# FOC_MCU.net
KiCad netlist of a schematic drawn in Altium Designer
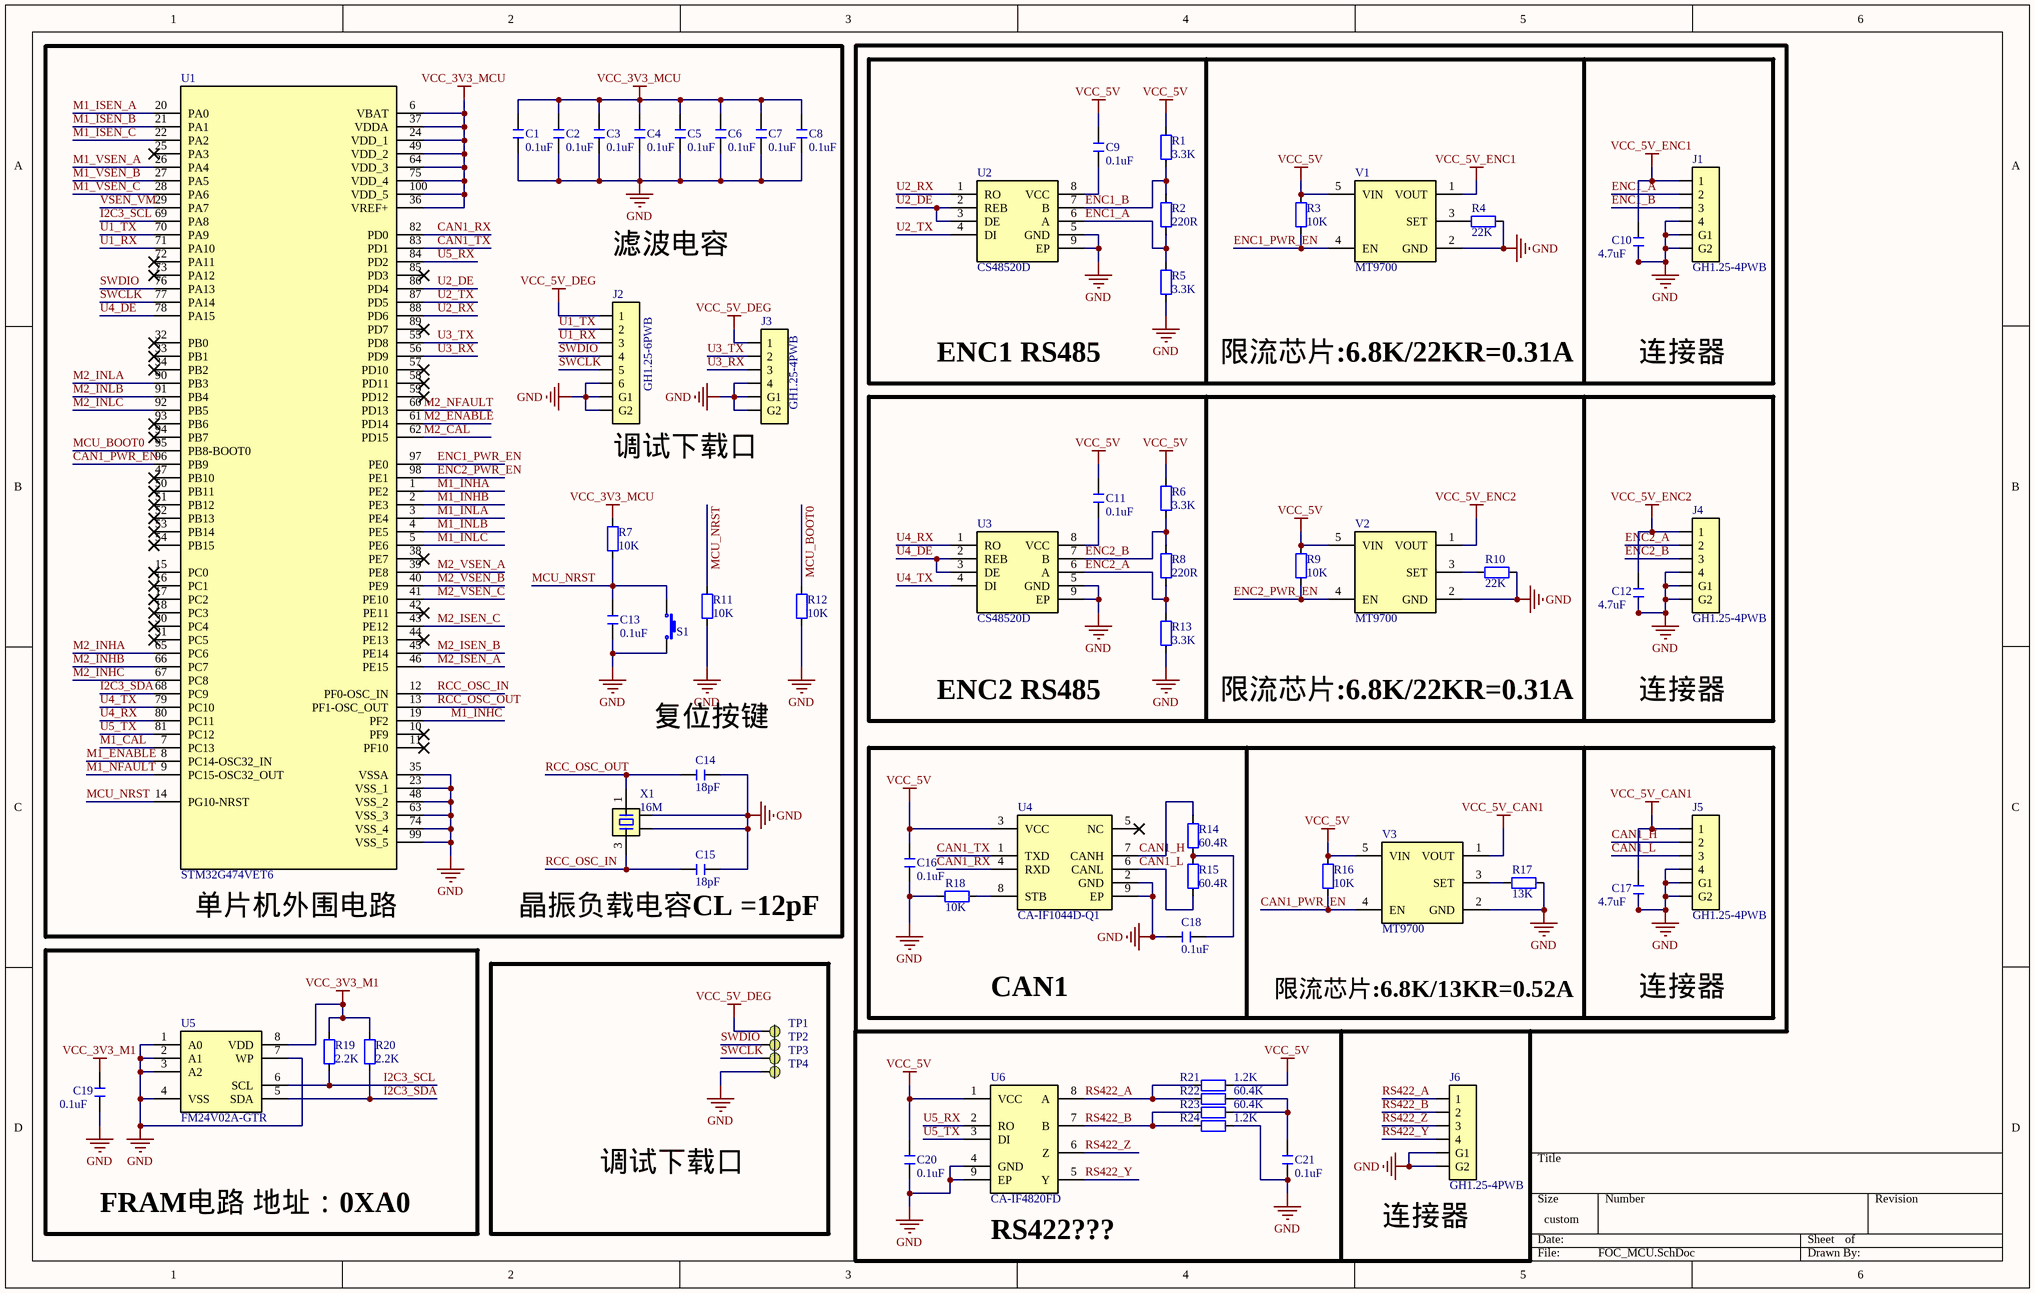
[diagram p0: FOC_MCU.SchDoc]

(export (version "E")
  (design (tool "Eeschema 10.0.6"))
  (components
    (comp (ref "C1")
      (value "0.1uF")
      (footprint "C 0603_L")
      (description "贴片电容")
      (libsource (lib "0.1 电阻_电容_电感") (part "C"))
    )
    (comp (ref "C2")
      (value "0.1uF")
      (footprint "C 0603_L")
      (description "贴片电容")
      (libsource (lib "0.1 电阻_电容_电感") (part "C"))
    )
    (comp (ref "C3")
      (value "0.1uF")
      (footprint "C 0603_L")
      (description "贴片电容")
      (libsource (lib "0.1 电阻_电容_电感") (part "C"))
    )
    (comp (ref "C4")
      (value "0.1uF")
      (footprint "C 0603_L")
      (description "贴片电容")
      (libsource (lib "0.1 电阻_电容_电感") (part "C"))
    )
    (comp (ref "C5")
      (value "0.1uF")
      (footprint "C 0603_L")
      (description "贴片电容")
      (libsource (lib "0.1 电阻_电容_电感") (part "C"))
    )
    (comp (ref "C6")
      (value "0.1uF")
      (footprint "C 0603_L")
      (description "贴片电容")
      (libsource (lib "0.1 电阻_电容_电感") (part "C"))
    )
    (comp (ref "C7")
      (value "0.1uF")
      (footprint "C 0603_L")
      (description "贴片电容")
      (libsource (lib "0.1 电阻_电容_电感") (part "C"))
    )
    (comp (ref "C8")
      (value "0.1uF")
      (footprint "C 0603_L")
      (description "贴片电容")
      (libsource (lib "0.1 电阻_电容_电感") (part "C"))
    )
    (comp (ref "C9")
      (value "0.1uF")
      (footprint "C 0603_L")
      (description "贴片电容")
      (libsource (lib "0.1 电阻_电容_电感") (part "C"))
    )
    (comp (ref "C10")
      (value "4.7uF")
      (footprint "C 0603_L")
      (description "贴片电容")
      (libsource (lib "0.1 电阻_电容_电感") (part "C"))
    )
    (comp (ref "C11")
      (value "0.1uF")
      (footprint "C 0603_L")
      (description "贴片电容")
      (libsource (lib "0.1 电阻_电容_电感") (part "C"))
    )
    (comp (ref "C12")
      (value "4.7uF")
      (footprint "C 0603_L")
      (description "贴片电容")
      (libsource (lib "0.1 电阻_电容_电感") (part "C"))
    )
    (comp (ref "C13")
      (value "0.1uF")
      (footprint "C 0603_L")
      (description "贴片电容")
      (libsource (lib "0.1 电阻_电容_电感") (part "C"))
    )
    (comp (ref "C14")
      (value "18pF")
      (footprint "C 0603_L")
      (description "贴片电容")
      (libsource (lib "0.1 电阻_电容_电感") (part "C"))
    )
    (comp (ref "C15")
      (value "18pF")
      (footprint "C 0603_L")
      (description "贴片电容")
      (libsource (lib "0.1 电阻_电容_电感") (part "C"))
    )
    (comp (ref "C16")
      (value "0.1uF")
      (footprint "C 0603_L")
      (description "贴片电容")
      (libsource (lib "0.1 电阻_电容_电感") (part "C"))
    )
    (comp (ref "C17")
      (value "4.7uF")
      (footprint "C 0603_L")
      (description "贴片电容")
      (libsource (lib "0.1 电阻_电容_电感") (part "C"))
    )
    (comp (ref "C18")
      (value "0.1uF")
      (footprint "C 0603_L")
      (description "贴片电容")
      (libsource (lib "0.1 电阻_电容_电感") (part "C"))
    )
    (comp (ref "C19")
      (value "0.1uF")
      (footprint "C 0603_L")
      (description "贴片电容")
      (libsource (lib "0.1 电阻_电容_电感") (part "C"))
    )
    (comp (ref "C20")
      (value "0.1uF")
      (footprint "C 0603_L")
      (description "贴片电容")
      (libsource (lib "0.1 电阻_电容_电感") (part "C"))
    )
    (comp (ref "C21")
      (value "0.1uF")
      (footprint "C 0603_L")
      (description "贴片电容")
      (libsource (lib "0.1 电阻_电容_电感") (part "C"))
    )
    (comp (ref "J1")
      (value "GH1.25-4PWB")
      (footprint "GH1.25-4PWB")
      (description "GH1.25-4P 卧贴")
      (libsource (lib "3.5 连接器") (part "GH1.25-4PWB"))
    )
    (comp (ref "J2")
      (value "GH1.25-6PWB")
      (footprint "GH1.25-6PWB")
      (description "GH1.25-6P 卧贴")
      (libsource (lib "3.5 连接器") (part "GH1.25-6PWB"))
    )
    (comp (ref "J3")
      (value "GH1.25-4PWB")
      (footprint "GH1.25-4PWB")
      (description "GH1.25-4P 卧贴")
      (libsource (lib "3.5 连接器") (part "GH1.25-4PWB"))
    )
    (comp (ref "J4")
      (value "GH1.25-4PWB")
      (footprint "GH1.25-4PWB")
      (description "GH1.25-4P 卧贴")
      (libsource (lib "3.5 连接器") (part "GH1.25-4PWB"))
    )
    (comp (ref "J5")
      (value "GH1.25-4PWB")
      (footprint "GH1.25-4PWB")
      (description "GH1.25-4P 卧贴")
      (libsource (lib "3.5 连接器") (part "GH1.25-4PWB"))
    )
    (comp (ref "J6")
      (value "GH1.25-4PWB")
      (footprint "GH1.25-4PWB")
      (description "GH1.25-4P 卧贴")
      (libsource (lib "3.5 连接器") (part "GH1.25-4PWB"))
    )
    (comp (ref "R1")
      (value "3.3K")
      (footprint "R 0603_L")
      (description "贴片电阻")
      (libsource (lib "") (part "R_1"))
    )
    (comp (ref "R2")
      (value "220R")
      (footprint "R 0603_L")
      (description "贴片电阻")
      (libsource (lib "") (part "R_1"))
    )
    (comp (ref "R3")
      (value "10K")
      (footprint "R 0603_L")
      (description "贴片电阻")
      (libsource (lib "") (part "R_1"))
    )
    (comp (ref "R4")
      (value "22K")
      (footprint "R 0603_L")
      (description "贴片电阻")
      (libsource (lib "0.1 电阻_电容_电感") (part "R"))
    )
    (comp (ref "R5")
      (value "3.3K")
      (footprint "R 0603_L")
      (description "贴片电阻")
      (libsource (lib "") (part "R_1"))
    )
    (comp (ref "R6")
      (value "3.3K")
      (footprint "R 0603_L")
      (description "贴片电阻")
      (libsource (lib "") (part "R_1"))
    )
    (comp (ref "R7")
      (value "10K")
      (footprint "R 0603_L")
      (description "贴片电阻")
      (libsource (lib "") (part "R_2"))
    )
    (comp (ref "R8")
      (value "220R")
      (footprint "R 0603_L")
      (description "贴片电阻")
      (libsource (lib "") (part "R_1"))
    )
    (comp (ref "R9")
      (value "10K")
      (footprint "R 0603_L")
      (description "贴片电阻")
      (libsource (lib "") (part "R_1"))
    )
    (comp (ref "R10")
      (value "22K")
      (footprint "R 0603_L")
      (description "贴片电阻")
      (libsource (lib "0.1 电阻_电容_电感") (part "R"))
    )
    (comp (ref "R11")
      (value "10K")
      (footprint "R 0603_L")
      (description "贴片电阻")
      (libsource (lib "") (part "R_2"))
    )
    (comp (ref "R12")
      (value "10K")
      (footprint "R 0603_L")
      (description "贴片电阻")
      (libsource (lib "") (part "R_2"))
    )
    (comp (ref "R13")
      (value "3.3K")
      (footprint "R 0603_L")
      (description "贴片电阻")
      (libsource (lib "") (part "R_1"))
    )
    (comp (ref "R14")
      (value "60.4R")
      (footprint "R 0603_L")
      (description "贴片电阻")
      (libsource (lib "") (part "R_2"))
    )
    (comp (ref "R15")
      (value "60.4R")
      (footprint "R 0603_L")
      (description "贴片电阻")
      (libsource (lib "") (part "R_2"))
    )
    (comp (ref "R16")
      (value "10K")
      (footprint "R 0603_L")
      (description "贴片电阻")
      (libsource (lib "") (part "R_1"))
    )
    (comp (ref "R17")
      (value "13K")
      (footprint "R 0603_L")
      (description "贴片电阻")
      (libsource (lib "0.1 电阻_电容_电感") (part "R"))
    )
    (comp (ref "R18")
      (value "10K")
      (footprint "R 0603_L")
      (description "贴片电阻")
      (libsource (lib "0.1 电阻_电容_电感") (part "R"))
    )
    (comp (ref "R19")
      (value "2.2K")
      (footprint "R 0603_L")
      (description "贴片电阻")
      (libsource (lib "") (part "R_1"))
    )
    (comp (ref "R20")
      (value "2.2K")
      (footprint "R 0603_L")
      (description "贴片电阻")
      (libsource (lib "") (part "R_1"))
    )
    (comp (ref "R21")
      (value "1.2K")
      (footprint "R 0603_L")
      (description "贴片电阻")
      (libsource (lib "0.1 电阻_电容_电感") (part "R"))
    )
    (comp (ref "R22")
      (value "60.4K")
      (footprint "R 0603_L")
      (description "贴片电阻")
      (libsource (lib "0.1 电阻_电容_电感") (part "R"))
    )
    (comp (ref "R23")
      (value "60.4K")
      (footprint "R 0603_L")
      (description "贴片电阻")
      (libsource (lib "0.1 电阻_电容_电感") (part "R"))
    )
    (comp (ref "R24")
      (value "1.2K")
      (footprint "R 0603_L")
      (description "贴片电阻")
      (libsource (lib "0.1 电阻_电容_电感") (part "R"))
    )
    (comp (ref "S1")
      (value "TS-1089S-02526")
      (footprint "SMD_TS-1089S")
      (libsource (lib "0.7 按键开关") (part "TS-1089S-02526"))
    )
    (comp (ref "TP1") (value "~") (footprint "TP_RECT_2x2") (libsource (lib "0.5 测试点-焊盘") (part "TP")))
    (comp (ref "TP2") (value "~") (footprint "TP_RECT_2x2") (libsource (lib "0.5 测试点-焊盘") (part "TP")))
    (comp (ref "TP3") (value "~") (footprint "TP_RECT_2x2") (libsource (lib "0.5 测试点-焊盘") (part "TP")))
    (comp (ref "TP4") (value "~") (footprint "TP_RECT_2x2") (libsource (lib "0.5 测试点-焊盘") (part "TP")))
    (comp (ref "U1")
      (value "STM32G474VET6")
      (footprint "LQFP100_L")
      (description "STM32G4系列微处理器")
      (libsource (lib "1.0 微处理器") (part "STM32G474VET6"))
    )
    (comp (ref "U2")
      (value "CS48520D")
      (footprint "DFN65P300X75-9N")
      (description "RS485")
      (libsource (lib "1.4 通信芯片") (part "CS48520D"))
    )
    (comp (ref "U3")
      (value "CS48520D")
      (footprint "DFN65P300X75-9N")
      (description "RS485")
      (libsource (lib "1.4 通信芯片") (part "CS48520D"))
    )
    (comp (ref "U4")
      (value "CA-IF1044D-Q1")
      (footprint "DFN65P300X75-9N")
      (description "CAN收发器，5Mbps")
      (libsource (lib "1.4 通信芯片") (part "CA-IF1044D-Q1"))
    )
    (comp (ref "U5")
      (value "FM24V02A-GTR")
      (footprint "SOIC-8N")
      (libsource (lib "1.5 存储芯片") (part "FM24V02A-GTR"))
    )
    (comp (ref "U6")
      (value "CA-IF4820FD")
      (footprint "DFN65P300X75-9N")
      (description "RS422，3.3V/5V，20Mbps")
      (libsource (lib "1.4 通信芯片") (part "CA-IF4820FD"))
    )
    (comp (ref "V1")
      (value "MT9700")
      (footprint "SOT-23-5")
      (description "功率电子开关")
      (libsource (lib "1.2 电源芯片") (part "MT9700"))
    )
    (comp (ref "V2")
      (value "MT9700")
      (footprint "SOT-23-5")
      (description "功率电子开关")
      (libsource (lib "1.2 电源芯片") (part "MT9700"))
    )
    (comp (ref "V3")
      (value "MT9700")
      (footprint "SOT-23-5")
      (description "功率电子开关")
      (libsource (lib "1.2 电源芯片") (part "MT9700"))
    )
    (comp (ref "X1")
      (value "16M")
      (footprint "OSC 2016-4P")
      (description "4脚无源晶振，负载电容12pF")
      (libsource (lib "0.9 晶振") (part "X201616MOB4SI"))
    )
  )
  (nets
    (net (code "1") (name "/CAN1_H") (class "Default")
      (node (ref "J5") (pin "2") (pinfunction "2_2") (pintype "passive"))
      (node (ref "R14") (pin "1") (pinfunction "1_1") (pintype "passive"))
      (node (ref "U4") (pin "7") (pinfunction "CANH_7") (pintype "passive"))
    )
    (net (code "2") (name "/CAN1_L") (class "Default")
      (node (ref "J5") (pin "3") (pinfunction "3_3") (pintype "passive"))
      (node (ref "R15") (pin "2") (pinfunction "2_2") (pintype "passive"))
      (node (ref "U4") (pin "6") (pinfunction "CANL_6") (pintype "passive"))
    )
    (net (code "3") (name "/CAN1_PWR_EN") (class "Default")
      (node (ref "R16") (pin "1") (pinfunction "1_1") (pintype "passive"))
      (node (ref "U1") (pin "96") (pinfunction "PB9_96") (pintype "passive"))
      (node (ref "V3") (pin "4") (pinfunction "EN_4") (pintype "passive"))
    )
    (net (code "4") (name "/CAN1_RX") (class "Default")
      (node (ref "U1") (pin "82") (pinfunction "PD0_82") (pintype "passive"))
      (node (ref "U4") (pin "4") (pinfunction "RXD_4") (pintype "power_in"))
    )
    (net (code "5") (name "/CAN1_TX") (class "Default")
      (node (ref "U1") (pin "83") (pinfunction "PD1_83") (pintype "passive"))
      (node (ref "U4") (pin "1") (pinfunction "TXD_1") (pintype "power_in"))
    )
    (net (code "6") (name "/ENC1_A") (class "Default")
      (node (ref "J1") (pin "2") (pinfunction "2_2") (pintype "passive"))
      (node (ref "R2") (pin "1") (pinfunction "1_1") (pintype "passive"))
      (node (ref "R5") (pin "2") (pinfunction "2_2") (pintype "passive"))
      (node (ref "U2") (pin "6") (pinfunction "A_6") (pintype "passive"))
    )
    (net (code "7") (name "/ENC1_B") (class "Default")
      (node (ref "J1") (pin "3") (pinfunction "3_3") (pintype "passive"))
      (node (ref "R1") (pin "1") (pinfunction "1_1") (pintype "passive"))
      (node (ref "R2") (pin "2") (pinfunction "2_2") (pintype "passive"))
      (node (ref "U2") (pin "7") (pinfunction "B_7") (pintype "passive"))
    )
    (net (code "8") (name "/ENC1_PWR_EN") (class "Default")
      (node (ref "R3") (pin "1") (pinfunction "1_1") (pintype "passive"))
      (node (ref "U1") (pin "97") (pinfunction "PE0_97") (pintype "passive"))
      (node (ref "V1") (pin "4") (pinfunction "EN_4") (pintype "passive"))
    )
    (net (code "9") (name "/ENC2_A") (class "Default")
      (node (ref "J4") (pin "2") (pinfunction "2_2") (pintype "passive"))
      (node (ref "R13") (pin "2") (pinfunction "2_2") (pintype "passive"))
      (node (ref "R8") (pin "1") (pinfunction "1_1") (pintype "passive"))
      (node (ref "U3") (pin "6") (pinfunction "A_6") (pintype "passive"))
    )
    (net (code "10") (name "/ENC2_B") (class "Default")
      (node (ref "J4") (pin "3") (pinfunction "3_3") (pintype "passive"))
      (node (ref "R6") (pin "1") (pinfunction "1_1") (pintype "passive"))
      (node (ref "R8") (pin "2") (pinfunction "2_2") (pintype "passive"))
      (node (ref "U3") (pin "7") (pinfunction "B_7") (pintype "passive"))
    )
    (net (code "11") (name "/ENC2_PWR_EN") (class "Default")
      (node (ref "R9") (pin "1") (pinfunction "1_1") (pintype "passive"))
      (node (ref "U1") (pin "98") (pinfunction "PE1_98") (pintype "passive"))
      (node (ref "V2") (pin "4") (pinfunction "EN_4") (pintype "passive"))
    )
    (net (code "12") (name "/I2C3_SCL") (class "Default")
      (node (ref "R19") (pin "1") (pinfunction "1_1") (pintype "passive"))
      (node (ref "U1") (pin "69") (pinfunction "PA8_69") (pintype "passive"))
      (node (ref "U5") (pin "6") (pinfunction "SCL_6") (pintype "passive"))
    )
    (net (code "13") (name "/I2C3_SDA") (class "Default")
      (node (ref "R20") (pin "1") (pinfunction "1_1") (pintype "passive"))
      (node (ref "U1") (pin "68") (pinfunction "PC9_68") (pintype "passive"))
      (node (ref "U5") (pin "5") (pinfunction "SDA_5") (pintype "passive"))
    )
    (net (code "14") (name "/M1_CAL") (class "Default")
      (node (ref "U1") (pin "7") (pinfunction "PC13_7") (pintype "passive"))
    )
    (net (code "15") (name "/M1_ENABLE") (class "Default")
      (node (ref "U1") (pin "8") (pinfunction "PC14-OSC32_IN_8") (pintype "passive"))
    )
    (net (code "16") (name "/M1_INHA") (class "Default")
      (node (ref "U1") (pin "1") (pinfunction "PE2_1") (pintype "passive"))
    )
    (net (code "17") (name "/M1_INHB") (class "Default")
      (node (ref "U1") (pin "2") (pinfunction "PE3_2") (pintype "passive"))
    )
    (net (code "18") (name "/M1_INHC") (class "Default")
      (node (ref "U1") (pin "19") (pinfunction "PF2_19") (pintype "passive"))
    )
    (net (code "19") (name "/M1_INLA") (class "Default")
      (node (ref "U1") (pin "3") (pinfunction "PE4_3") (pintype "passive"))
    )
    (net (code "20") (name "/M1_INLB") (class "Default")
      (node (ref "U1") (pin "4") (pinfunction "PE5_4") (pintype "passive"))
    )
    (net (code "21") (name "/M1_INLC") (class "Default")
      (node (ref "U1") (pin "5") (pinfunction "PE6_5") (pintype "passive"))
    )
    (net (code "22") (name "/M1_ISEN_A") (class "Default")
      (node (ref "U1") (pin "20") (pinfunction "PA0_20") (pintype "passive"))
    )
    (net (code "23") (name "/M1_ISEN_B") (class "Default")
      (node (ref "U1") (pin "21") (pinfunction "PA1_21") (pintype "passive"))
    )
    (net (code "24") (name "/M1_ISEN_C") (class "Default")
      (node (ref "U1") (pin "22") (pinfunction "PA2_22") (pintype "passive"))
    )
    (net (code "25") (name "/M1_NFAULT") (class "Default")
      (node (ref "U1") (pin "9") (pinfunction "PC15-OSC32_OUT_9") (pintype "passive"))
    )
    (net (code "26") (name "/M1_VSEN_A") (class "Default")
      (node (ref "U1") (pin "26") (pinfunction "PA4_26") (pintype "passive"))
    )
    (net (code "27") (name "/M1_VSEN_B") (class "Default")
      (node (ref "U1") (pin "27") (pinfunction "PA5_27") (pintype "passive"))
    )
    (net (code "28") (name "/M1_VSEN_C") (class "Default")
      (node (ref "U1") (pin "28") (pinfunction "PA6_28") (pintype "passive"))
    )
    (net (code "29") (name "/M2_CAL") (class "Default")
      (node (ref "U1") (pin "62") (pinfunction "PD15_62") (pintype "passive"))
    )
    (net (code "30") (name "/M2_ENABLE") (class "Default")
      (node (ref "U1") (pin "61") (pinfunction "PD14_61") (pintype "passive"))
    )
    (net (code "31") (name "/M2_INHA") (class "Default")
      (node (ref "U1") (pin "65") (pinfunction "PC6_65") (pintype "passive"))
    )
    (net (code "32") (name "/M2_INHB") (class "Default")
      (node (ref "U1") (pin "66") (pinfunction "PC7_66") (pintype "passive"))
    )
    (net (code "33") (name "/M2_INHC") (class "Default")
      (node (ref "U1") (pin "67") (pinfunction "PC8_67") (pintype "passive"))
    )
    (net (code "34") (name "/M2_INLA") (class "Default")
      (node (ref "U1") (pin "90") (pinfunction "PB3_90") (pintype "passive"))
    )
    (net (code "35") (name "/M2_INLB") (class "Default")
      (node (ref "U1") (pin "91") (pinfunction "PB4_91") (pintype "passive"))
    )
    (net (code "36") (name "/M2_INLC") (class "Default")
      (node (ref "U1") (pin "92") (pinfunction "PB5_92") (pintype "passive"))
    )
    (net (code "37") (name "/M2_ISEN_A") (class "Default")
      (node (ref "U1") (pin "46") (pinfunction "PE15_46") (pintype "passive"))
    )
    (net (code "38") (name "/M2_ISEN_B") (class "Default")
      (node (ref "U1") (pin "45") (pinfunction "PE14_45") (pintype "passive"))
    )
    (net (code "39") (name "/M2_ISEN_C") (class "Default")
      (node (ref "U1") (pin "43") (pinfunction "PE12_43") (pintype "passive"))
    )
    (net (code "40") (name "/M2_NFAULT") (class "Default")
      (node (ref "U1") (pin "60") (pinfunction "PD13_60") (pintype "passive"))
    )
    (net (code "41") (name "/M2_VSEN_A") (class "Default")
      (node (ref "U1") (pin "39") (pinfunction "PE8_39") (pintype "passive"))
    )
    (net (code "42") (name "/M2_VSEN_B") (class "Default")
      (node (ref "U1") (pin "40") (pinfunction "PE9_40") (pintype "passive"))
    )
    (net (code "43") (name "/M2_VSEN_C") (class "Default")
      (node (ref "U1") (pin "41") (pinfunction "PE10_41") (pintype "passive"))
    )
    (net (code "44") (name "/MCU_BOOT0") (class "Default")
      (node (ref "R12") (pin "1") (pinfunction "1_1") (pintype "passive"))
      (node (ref "U1") (pin "95") (pinfunction "PB8-BOOT0_95") (pintype "passive"))
    )
    (net (code "45") (name "/MCU_NRST") (class "Default")
      (node (ref "C13") (pin "1") (pinfunction "1_1") (pintype "passive"))
      (node (ref "R11") (pin "1") (pinfunction "1_1") (pintype "passive"))
      (node (ref "R7") (pin "2") (pinfunction "2_2") (pintype "passive"))
      (node (ref "S1") (pin "2") (pinfunction "2_2") (pintype "passive"))
      (node (ref "U1") (pin "14") (pinfunction "PG10-NRST_14") (pintype "passive"))
    )
    (net (code "46") (name "/RCC_OSC_IN") (class "Default")
      (node (ref "C15") (pin "2") (pinfunction "2_2") (pintype "passive"))
      (node (ref "U1") (pin "12") (pinfunction "PF0-OSC_IN_12") (pintype "passive"))
      (node (ref "X1") (pin "3") (pinfunction "3_3") (pintype "passive"))
    )
    (net (code "47") (name "/RCC_OSC_OUT") (class "Default")
      (node (ref "C14") (pin "2") (pinfunction "2_2") (pintype "passive"))
      (node (ref "U1") (pin "13") (pinfunction "PF1-OSC_OUT_13") (pintype "passive"))
      (node (ref "X1") (pin "1") (pinfunction "1_1") (pintype "passive"))
    )
    (net (code "48") (name "/RS422_A") (class "Default")
      (node (ref "J6") (pin "1") (pinfunction "1_1") (pintype "passive"))
      (node (ref "R21") (pin "2") (pinfunction "2_2") (pintype "passive"))
      (node (ref "R22") (pin "2") (pinfunction "2_2") (pintype "passive"))
      (node (ref "U6") (pin "8") (pinfunction "A_8") (pintype "passive"))
    )
    (net (code "49") (name "/RS422_B") (class "Default")
      (node (ref "J6") (pin "2") (pinfunction "2_2") (pintype "passive"))
      (node (ref "R23") (pin "2") (pinfunction "2_2") (pintype "passive"))
      (node (ref "R24") (pin "2") (pinfunction "2_2") (pintype "passive"))
      (node (ref "U6") (pin "7") (pinfunction "B_7") (pintype "passive"))
    )
    (net (code "50") (name "/RS422_Y") (class "Default")
      (node (ref "J6") (pin "4") (pinfunction "4_4") (pintype "passive"))
      (node (ref "U6") (pin "5") (pinfunction "Y_5") (pintype "passive"))
    )
    (net (code "51") (name "/RS422_Z") (class "Default")
      (node (ref "J6") (pin "3") (pinfunction "3_3") (pintype "passive"))
      (node (ref "U6") (pin "6") (pinfunction "Z_6") (pintype "passive"))
    )
    (net (code "52") (name "/SWCLK") (class "Default")
      (node (ref "J2") (pin "5") (pinfunction "5_5") (pintype "passive"))
      (node (ref "TP3") (pin "1") (pintype "passive"))
      (node (ref "U1") (pin "77") (pinfunction "PA14_77") (pintype "passive"))
    )
    (net (code "53") (name "/SWDIO") (class "Default")
      (node (ref "J2") (pin "4") (pinfunction "4_4") (pintype "passive"))
      (node (ref "TP2") (pin "1") (pintype "passive"))
      (node (ref "U1") (pin "76") (pinfunction "PA13_76") (pintype "passive"))
    )
    (net (code "54") (name "/U1_RX") (class "Default")
      (node (ref "J2") (pin "3") (pinfunction "3_3") (pintype "passive"))
      (node (ref "U1") (pin "71") (pinfunction "PA10_71") (pintype "passive"))
    )
    (net (code "55") (name "/U1_TX") (class "Default")
      (node (ref "J2") (pin "2") (pinfunction "2_2") (pintype "passive"))
      (node (ref "U1") (pin "70") (pinfunction "PA9_70") (pintype "passive"))
    )
    (net (code "56") (name "/U2_DE") (class "Default")
      (node (ref "U1") (pin "86") (pinfunction "PD4_86") (pintype "passive"))
      (node (ref "U2") (pin "2") (pinfunction "REB_2") (pintype "passive"))
      (node (ref "U2") (pin "3") (pinfunction "DE_3") (pintype "passive"))
    )
    (net (code "57") (name "/U2_RX") (class "Default")
      (node (ref "U1") (pin "88") (pinfunction "PD6_88") (pintype "passive"))
      (node (ref "U2") (pin "1") (pinfunction "RO_1") (pintype "power_in"))
    )
    (net (code "58") (name "/U2_TX") (class "Default")
      (node (ref "U1") (pin "87") (pinfunction "PD5_87") (pintype "passive"))
      (node (ref "U2") (pin "4") (pinfunction "DI_4") (pintype "power_in"))
    )
    (net (code "59") (name "/U3_RX") (class "Default")
      (node (ref "J3") (pin "3") (pinfunction "3_3") (pintype "passive"))
      (node (ref "U1") (pin "56") (pinfunction "PD9_56") (pintype "passive"))
    )
    (net (code "60") (name "/U3_TX") (class "Default")
      (node (ref "J3") (pin "2") (pinfunction "2_2") (pintype "passive"))
      (node (ref "U1") (pin "55") (pinfunction "PD8_55") (pintype "passive"))
    )
    (net (code "61") (name "/U4_DE") (class "Default")
      (node (ref "U1") (pin "78") (pinfunction "PA15_78") (pintype "passive"))
      (node (ref "U3") (pin "2") (pinfunction "REB_2") (pintype "passive"))
      (node (ref "U3") (pin "3") (pinfunction "DE_3") (pintype "passive"))
    )
    (net (code "62") (name "/U4_RX") (class "Default")
      (node (ref "U1") (pin "80") (pinfunction "PC11_80") (pintype "passive"))
      (node (ref "U3") (pin "1") (pinfunction "RO_1") (pintype "power_in"))
    )
    (net (code "63") (name "/U4_TX") (class "Default")
      (node (ref "U1") (pin "79") (pinfunction "PC10_79") (pintype "passive"))
      (node (ref "U3") (pin "4") (pinfunction "DI_4") (pintype "power_in"))
    )
    (net (code "64") (name "/U5_RX") (class "Default")
      (node (ref "U1") (pin "84") (pinfunction "PD2_84") (pintype "passive"))
      (node (ref "U6") (pin "2") (pinfunction "RO_2") (pintype "passive"))
    )
    (net (code "65") (name "/U5_TX") (class "Default")
      (node (ref "U1") (pin "81") (pinfunction "PC12_81") (pintype "passive"))
      (node (ref "U6") (pin "3") (pinfunction "DI_3") (pintype "passive"))
    )
    (net (code "66") (name "/VSEN_VM") (class "Default")
      (node (ref "U1") (pin "29") (pinfunction "PA7_29") (pintype "passive"))
    )
    (net (code "67") (name "GND") (class "Default")
      (node (ref "C1") (pin "2") (pinfunction "2_2") (pintype "passive"))
      (node (ref "C10") (pin "1") (pinfunction "1_1") (pintype "passive"))
      (node (ref "C12") (pin "1") (pinfunction "1_1") (pintype "passive"))
      (node (ref "C13") (pin "2") (pinfunction "2_2") (pintype "passive"))
      (node (ref "C14") (pin "1") (pinfunction "1_1") (pintype "passive"))
      (node (ref "C15") (pin "1") (pinfunction "1_1") (pintype "passive"))
      (node (ref "C16") (pin "1") (pinfunction "1_1") (pintype "passive"))
      (node (ref "C17") (pin "1") (pinfunction "1_1") (pintype "passive"))
      (node (ref "C18") (pin "1") (pinfunction "1_1") (pintype "passive"))
      (node (ref "C19") (pin "1") (pinfunction "1_1") (pintype "passive"))
      (node (ref "C2") (pin "2") (pinfunction "2_2") (pintype "passive"))
      (node (ref "C20") (pin "1") (pinfunction "1_1") (pintype "passive"))
      (node (ref "C21") (pin "1") (pinfunction "1_1") (pintype "passive"))
      (node (ref "C3") (pin "2") (pinfunction "2_2") (pintype "passive"))
      (node (ref "C4") (pin "2") (pinfunction "2_2") (pintype "passive"))
      (node (ref "C5") (pin "2") (pinfunction "2_2") (pintype "passive"))
      (node (ref "C6") (pin "2") (pinfunction "2_2") (pintype "passive"))
      (node (ref "C7") (pin "2") (pinfunction "2_2") (pintype "passive"))
      (node (ref "C8") (pin "2") (pinfunction "2_2") (pintype "passive"))
      (node (ref "J1") (pin "4") (pinfunction "4_4") (pintype "passive"))
      (node (ref "J1") (pin "G1") (pinfunction "G1_G1") (pintype "passive"))
      (node (ref "J1") (pin "G2") (pinfunction "G2_G2") (pintype "passive"))
      (node (ref "J2") (pin "6") (pinfunction "6_6") (pintype "passive"))
      (node (ref "J2") (pin "G1") (pinfunction "G1_G1") (pintype "passive"))
      (node (ref "J2") (pin "G2") (pinfunction "G2_G2") (pintype "passive"))
      (node (ref "J3") (pin "4") (pinfunction "4_4") (pintype "passive"))
      (node (ref "J3") (pin "G1") (pinfunction "G1_G1") (pintype "passive"))
      (node (ref "J3") (pin "G2") (pinfunction "G2_G2") (pintype "passive"))
      (node (ref "J4") (pin "4") (pinfunction "4_4") (pintype "passive"))
      (node (ref "J4") (pin "G1") (pinfunction "G1_G1") (pintype "passive"))
      (node (ref "J4") (pin "G2") (pinfunction "G2_G2") (pintype "passive"))
      (node (ref "J5") (pin "4") (pinfunction "4_4") (pintype "passive"))
      (node (ref "J5") (pin "G1") (pinfunction "G1_G1") (pintype "passive"))
      (node (ref "J5") (pin "G2") (pinfunction "G2_G2") (pintype "passive"))
      (node (ref "J6") (pin "G1") (pinfunction "G1_G1") (pintype "passive"))
      (node (ref "J6") (pin "G2") (pinfunction "G2_G2") (pintype "passive"))
      (node (ref "R10") (pin "1") (pinfunction "1_1") (pintype "passive"))
      (node (ref "R11") (pin "2") (pinfunction "2_2") (pintype "passive"))
      (node (ref "R12") (pin "2") (pinfunction "2_2") (pintype "passive"))
      (node (ref "R13") (pin "1") (pinfunction "1_1") (pintype "passive"))
      (node (ref "R17") (pin "1") (pinfunction "1_1") (pintype "passive"))
      (node (ref "R18") (pin "2") (pinfunction "2_2") (pintype "passive"))
      (node (ref "R24") (pin "1") (pinfunction "1_1") (pintype "passive"))
      (node (ref "R4") (pin "1") (pinfunction "1_1") (pintype "passive"))
      (node (ref "R5") (pin "1") (pinfunction "1_1") (pintype "passive"))
      (node (ref "S1") (pin "1") (pinfunction "1_1") (pintype "passive"))
      (node (ref "TP4") (pin "1") (pintype "passive"))
      (node (ref "U1") (pin "23") (pinfunction "VSS_1_23") (pintype "passive"))
      (node (ref "U1") (pin "35") (pinfunction "VSSA_35") (pintype "passive"))
      (node (ref "U1") (pin "48") (pinfunction "VSS_2_48") (pintype "passive"))
      (node (ref "U1") (pin "63") (pinfunction "VSS_3_63") (pintype "passive"))
      (node (ref "U1") (pin "74") (pinfunction "VSS_4_74") (pintype "passive"))
      (node (ref "U1") (pin "99") (pinfunction "VSS_5_99") (pintype "passive"))
      (node (ref "U2") (pin "5") (pinfunction "GND_5") (pintype "passive"))
      (node (ref "U2") (pin "9") (pinfunction "EP_9") (pintype "passive"))
      (node (ref "U3") (pin "5") (pinfunction "GND_5") (pintype "passive"))
      (node (ref "U3") (pin "9") (pinfunction "EP_9") (pintype "passive"))
      (node (ref "U4") (pin "2") (pinfunction "GND_2") (pintype "passive"))
      (node (ref "U4") (pin "9") (pinfunction "EP_9") (pintype "passive"))
      (node (ref "U5") (pin "1") (pinfunction "A0_1") (pintype "passive"))
      (node (ref "U5") (pin "2") (pinfunction "A1_2") (pintype "passive"))
      (node (ref "U5") (pin "3") (pinfunction "A2_3") (pintype "passive"))
      (node (ref "U5") (pin "4") (pinfunction "VSS_4") (pintype "power_in"))
      (node (ref "U5") (pin "7") (pinfunction "WP_7") (pintype "passive"))
      (node (ref "U6") (pin "4") (pinfunction "GND_4") (pintype "power_in"))
      (node (ref "U6") (pin "9") (pinfunction "EP_9") (pintype "power_in"))
      (node (ref "V1") (pin "2") (pinfunction "GND_2") (pintype "passive"))
      (node (ref "V2") (pin "2") (pinfunction "GND_2") (pintype "passive"))
      (node (ref "V3") (pin "2") (pinfunction "GND_2") (pintype "passive"))
      (node (ref "X1") (pin "2") (pinfunction "2_2") (pintype "passive"))
      (node (ref "X1") (pin "4") (pinfunction "4_4") (pintype "passive"))
    )
    (net (code "68") (name "Net-(C18-Pad2)") (class "Default")
      (node (ref "C18") (pin "2") (pinfunction "2_2") (pintype "passive"))
      (node (ref "R14") (pin "2") (pinfunction "2_2") (pintype "passive"))
      (node (ref "R15") (pin "1") (pinfunction "1_1") (pintype "passive"))
    )
    (net (code "69") (name "Net-(C21-Pad2)") (class "Default")
      (node (ref "C21") (pin "2") (pinfunction "2_2") (pintype "passive"))
      (node (ref "R22") (pin "1") (pinfunction "1_1") (pintype "passive"))
      (node (ref "R23") (pin "1") (pinfunction "1_1") (pintype "passive"))
    )
    (net (code "70") (name "Net-(U2-VCC)") (class "Default")
      (node (ref "C9") (pin "1") (pinfunction "1_1") (pintype "passive"))
      (node (ref "U2") (pin "8") (pinfunction "VCC_8") (pintype "passive"))
    )
    (net (code "71") (name "Net-(U3-VCC)") (class "Default")
      (node (ref "C11") (pin "1") (pinfunction "1_1") (pintype "passive"))
      (node (ref "U3") (pin "8") (pinfunction "VCC_8") (pintype "passive"))
    )
    (net (code "72") (name "Net-(U4-STB)") (class "Default")
      (node (ref "R18") (pin "1") (pinfunction "1_1") (pintype "passive"))
      (node (ref "U4") (pin "8") (pinfunction "STB_8") (pintype "passive"))
    )
    (net (code "73") (name "Net-(V1-SET)") (class "Default")
      (node (ref "R4") (pin "2") (pinfunction "2_2") (pintype "passive"))
      (node (ref "V1") (pin "3") (pinfunction "SET_3") (pintype "passive"))
    )
    (net (code "74") (name "Net-(V2-SET)") (class "Default")
      (node (ref "R10") (pin "2") (pinfunction "2_2") (pintype "passive"))
      (node (ref "V2") (pin "3") (pinfunction "SET_3") (pintype "passive"))
    )
    (net (code "75") (name "Net-(V3-SET)") (class "Default")
      (node (ref "R17") (pin "2") (pinfunction "2_2") (pintype "passive"))
      (node (ref "V3") (pin "3") (pinfunction "SET_3") (pintype "passive"))
    )
    (net (code "76") (name "VCC_3V3_M1") (class "Default")
      (node (ref "C19") (pin "2") (pinfunction "2_2") (pintype "passive"))
      (node (ref "R19") (pin "2") (pinfunction "2_2") (pintype "passive"))
      (node (ref "R20") (pin "2") (pinfunction "2_2") (pintype "passive"))
      (node (ref "U5") (pin "8") (pinfunction "VDD_8") (pintype "power_in"))
    )
    (net (code "77") (name "VCC_3V3_MCU") (class "Default")
      (node (ref "C1") (pin "1") (pinfunction "1_1") (pintype "passive"))
      (node (ref "C2") (pin "1") (pinfunction "1_1") (pintype "passive"))
      (node (ref "C3") (pin "1") (pinfunction "1_1") (pintype "passive"))
      (node (ref "C4") (pin "1") (pinfunction "1_1") (pintype "passive"))
      (node (ref "C5") (pin "1") (pinfunction "1_1") (pintype "passive"))
      (node (ref "C6") (pin "1") (pinfunction "1_1") (pintype "passive"))
      (node (ref "C7") (pin "1") (pinfunction "1_1") (pintype "passive"))
      (node (ref "C8") (pin "1") (pinfunction "1_1") (pintype "passive"))
      (node (ref "R7") (pin "1") (pinfunction "1_1") (pintype "passive"))
      (node (ref "U1") (pin "100") (pinfunction "VDD_5_100") (pintype "passive"))
      (node (ref "U1") (pin "24") (pinfunction "VDD_1_24") (pintype "passive"))
      (node (ref "U1") (pin "36") (pinfunction "VREF+_36") (pintype "passive"))
      (node (ref "U1") (pin "37") (pinfunction "VDDA_37") (pintype "passive"))
      (node (ref "U1") (pin "49") (pinfunction "VDD_2_49") (pintype "passive"))
      (node (ref "U1") (pin "6") (pinfunction "VBAT_6") (pintype "passive"))
      (node (ref "U1") (pin "64") (pinfunction "VDD_3_64") (pintype "passive"))
      (node (ref "U1") (pin "75") (pinfunction "VDD_4_75") (pintype "passive"))
    )
    (net (code "78") (name "VCC_5V") (class "Default")
      (node (ref "C11") (pin "2") (pinfunction "2_2") (pintype "passive"))
      (node (ref "C16") (pin "2") (pinfunction "2_2") (pintype "passive"))
      (node (ref "C20") (pin "2") (pinfunction "2_2") (pintype "passive"))
      (node (ref "C9") (pin "2") (pinfunction "2_2") (pintype "passive"))
      (node (ref "R1") (pin "2") (pinfunction "2_2") (pintype "passive"))
      (node (ref "R16") (pin "2") (pinfunction "2_2") (pintype "passive"))
      (node (ref "R21") (pin "1") (pinfunction "1_1") (pintype "passive"))
      (node (ref "R3") (pin "2") (pinfunction "2_2") (pintype "passive"))
      (node (ref "R6") (pin "2") (pinfunction "2_2") (pintype "passive"))
      (node (ref "R9") (pin "2") (pinfunction "2_2") (pintype "passive"))
      (node (ref "U4") (pin "3") (pinfunction "VCC_3") (pintype "passive"))
      (node (ref "U6") (pin "1") (pinfunction "VCC_1") (pintype "power_in"))
      (node (ref "V1") (pin "5") (pinfunction "VIN_5") (pintype "passive"))
      (node (ref "V2") (pin "5") (pinfunction "VIN_5") (pintype "passive"))
      (node (ref "V3") (pin "5") (pinfunction "VIN_5") (pintype "passive"))
    )
    (net (code "79") (name "VCC_5V_CAN1") (class "Default")
      (node (ref "C17") (pin "2") (pinfunction "2_2") (pintype "passive"))
      (node (ref "J5") (pin "1") (pinfunction "1_1") (pintype "passive"))
      (node (ref "V3") (pin "1") (pinfunction "VOUT_1") (pintype "passive"))
    )
    (net (code "80") (name "VCC_5V_DEG") (class "Default")
      (node (ref "J2") (pin "1") (pinfunction "1_1") (pintype "passive"))
      (node (ref "J3") (pin "1") (pinfunction "1_1") (pintype "passive"))
      (node (ref "TP1") (pin "1") (pintype "passive"))
    )
    (net (code "81") (name "VCC_5V_ENC1") (class "Default")
      (node (ref "C10") (pin "2") (pinfunction "2_2") (pintype "passive"))
      (node (ref "J1") (pin "1") (pinfunction "1_1") (pintype "passive"))
      (node (ref "V1") (pin "1") (pinfunction "VOUT_1") (pintype "passive"))
    )
    (net (code "82") (name "VCC_5V_ENC2") (class "Default")
      (node (ref "C12") (pin "2") (pinfunction "2_2") (pintype "passive"))
      (node (ref "J4") (pin "1") (pinfunction "1_1") (pintype "passive"))
      (node (ref "V2") (pin "1") (pinfunction "VOUT_1") (pintype "passive"))
    )
    (net (code "83") (name "unconnected-(U1-PA3-Pad25)") (class "Default")
      (node (ref "U1") (pin "25") (pinfunction "PA3_25") (pintype "passive+no_connect"))
    )
    (net (code "84") (name "unconnected-(U1-PA11-Pad72)") (class "Default")
      (node (ref "U1") (pin "72") (pinfunction "PA11_72") (pintype "passive+no_connect"))
    )
    (net (code "85") (name "unconnected-(U1-PA12-Pad73)") (class "Default")
      (node (ref "U1") (pin "73") (pinfunction "PA12_73") (pintype "passive+no_connect"))
    )
    (net (code "86") (name "unconnected-(U1-PB0-Pad32)") (class "Default")
      (node (ref "U1") (pin "32") (pinfunction "PB0_32") (pintype "passive+no_connect"))
    )
    (net (code "87") (name "unconnected-(U1-PB1-Pad33)") (class "Default")
      (node (ref "U1") (pin "33") (pinfunction "PB1_33") (pintype "passive+no_connect"))
    )
    (net (code "88") (name "unconnected-(U1-PB2-Pad34)") (class "Default")
      (node (ref "U1") (pin "34") (pinfunction "PB2_34") (pintype "passive+no_connect"))
    )
    (net (code "89") (name "unconnected-(U1-PB6-Pad93)") (class "Default")
      (node (ref "U1") (pin "93") (pinfunction "PB6_93") (pintype "passive+no_connect"))
    )
    (net (code "90") (name "unconnected-(U1-PB7-Pad94)") (class "Default")
      (node (ref "U1") (pin "94") (pinfunction "PB7_94") (pintype "passive+no_connect"))
    )
    (net (code "91") (name "unconnected-(U1-PB10-Pad47)") (class "Default")
      (node (ref "U1") (pin "47") (pinfunction "PB10_47") (pintype "passive+no_connect"))
    )
    (net (code "92") (name "unconnected-(U1-PB11-Pad50)") (class "Default")
      (node (ref "U1") (pin "50") (pinfunction "PB11_50") (pintype "passive+no_connect"))
    )
    (net (code "93") (name "unconnected-(U1-PB12-Pad51)") (class "Default")
      (node (ref "U1") (pin "51") (pinfunction "PB12_51") (pintype "passive+no_connect"))
    )
    (net (code "94") (name "unconnected-(U1-PB13-Pad52)") (class "Default")
      (node (ref "U1") (pin "52") (pinfunction "PB13_52") (pintype "passive+no_connect"))
    )
    (net (code "95") (name "unconnected-(U1-PB14-Pad53)") (class "Default")
      (node (ref "U1") (pin "53") (pinfunction "PB14_53") (pintype "passive+no_connect"))
    )
    (net (code "96") (name "unconnected-(U1-PB15-Pad54)") (class "Default")
      (node (ref "U1") (pin "54") (pinfunction "PB15_54") (pintype "passive+no_connect"))
    )
    (net (code "97") (name "unconnected-(U1-PC0-Pad15)") (class "Default")
      (node (ref "U1") (pin "15") (pinfunction "PC0_15") (pintype "passive+no_connect"))
    )
    (net (code "98") (name "unconnected-(U1-PC1-Pad16)") (class "Default")
      (node (ref "U1") (pin "16") (pinfunction "PC1_16") (pintype "passive+no_connect"))
    )
    (net (code "99") (name "unconnected-(U1-PC2-Pad17)") (class "Default")
      (node (ref "U1") (pin "17") (pinfunction "PC2_17") (pintype "passive+no_connect"))
    )
    (net (code "100") (name "unconnected-(U1-PC3-Pad18)") (class "Default")
      (node (ref "U1") (pin "18") (pinfunction "PC3_18") (pintype "passive+no_connect"))
    )
    (net (code "101") (name "unconnected-(U1-PC4-Pad30)") (class "Default")
      (node (ref "U1") (pin "30") (pinfunction "PC4_30") (pintype "passive+no_connect"))
    )
    (net (code "102") (name "unconnected-(U1-PC5-Pad31)") (class "Default")
      (node (ref "U1") (pin "31") (pinfunction "PC5_31") (pintype "passive+no_connect"))
    )
    (net (code "103") (name "unconnected-(U1-PD3-Pad85)") (class "Default")
      (node (ref "U1") (pin "85") (pinfunction "PD3_85") (pintype "passive+no_connect"))
    )
    (net (code "104") (name "unconnected-(U1-PD7-Pad89)") (class "Default")
      (node (ref "U1") (pin "89") (pinfunction "PD7_89") (pintype "passive+no_connect"))
    )
    (net (code "105") (name "unconnected-(U1-PD10-Pad57)") (class "Default")
      (node (ref "U1") (pin "57") (pinfunction "PD10_57") (pintype "passive+no_connect"))
    )
    (net (code "106") (name "unconnected-(U1-PD11-Pad58)") (class "Default")
      (node (ref "U1") (pin "58") (pinfunction "PD11_58") (pintype "passive+no_connect"))
    )
    (net (code "107") (name "unconnected-(U1-PD12-Pad59)") (class "Default")
      (node (ref "U1") (pin "59") (pinfunction "PD12_59") (pintype "passive+no_connect"))
    )
    (net (code "108") (name "unconnected-(U1-PE7-Pad38)") (class "Default")
      (node (ref "U1") (pin "38") (pinfunction "PE7_38") (pintype "passive+no_connect"))
    )
    (net (code "109") (name "unconnected-(U1-PE11-Pad42)") (class "Default")
      (node (ref "U1") (pin "42") (pinfunction "PE11_42") (pintype "passive+no_connect"))
    )
    (net (code "110") (name "unconnected-(U1-PE13-Pad44)") (class "Default")
      (node (ref "U1") (pin "44") (pinfunction "PE13_44") (pintype "passive+no_connect"))
    )
    (net (code "111") (name "unconnected-(U1-PF9-Pad10)") (class "Default")
      (node (ref "U1") (pin "10") (pinfunction "PF9_10") (pintype "passive+no_connect"))
    )
    (net (code "112") (name "unconnected-(U1-PF10-Pad11)") (class "Default")
      (node (ref "U1") (pin "11") (pinfunction "PF10_11") (pintype "passive+no_connect"))
    )
    (net (code "113") (name "unconnected-(U4-NC-Pad5)") (class "Default")
      (node (ref "U4") (pin "5") (pinfunction "NC_5") (pintype "passive+no_connect"))
    )
  )
)
